# tiny_midi_brk.net
KiCad netlist of a schematic drawn in EAGLE
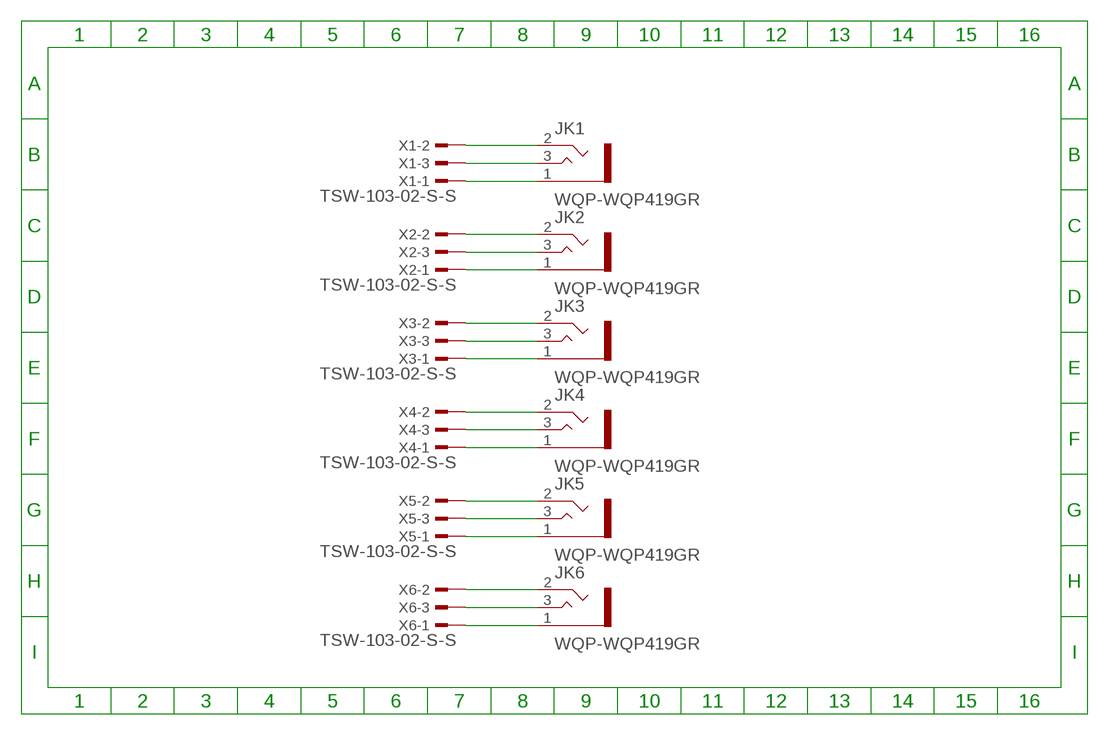
[diagram p0: schematic, sheet 1]

(export (version "E")
  (design (tool "Eeschema 10.0.6"))
  (components
    (comp (ref "JK1")
      (value "WQP-WQP419GR")
      (footprint "eagle-import:WQP-PJ301M-12_JACK_TRS")
      (libsource (lib "eagle-import") (part "WQP-WQP419GR"))
    )
    (comp (ref "JK2")
      (value "WQP-WQP419GR")
      (footprint "eagle-import:WQP-PJ301M-12_JACK_TRS")
      (libsource (lib "eagle-import") (part "WQP-WQP419GR"))
    )
    (comp (ref "JK3")
      (value "WQP-WQP419GR")
      (footprint "eagle-import:WQP-PJ301M-12_JACK_TRS")
      (libsource (lib "eagle-import") (part "WQP-WQP419GR"))
    )
    (comp (ref "JK4")
      (value "WQP-WQP419GR")
      (footprint "eagle-import:WQP-PJ301M-12_JACK_TRS")
      (libsource (lib "eagle-import") (part "WQP-WQP419GR"))
    )
    (comp (ref "JK5")
      (value "WQP-WQP419GR")
      (footprint "eagle-import:WQP-PJ301M-12_JACK_TRS")
      (libsource (lib "eagle-import") (part "WQP-WQP419GR"))
    )
    (comp (ref "JK6")
      (value "WQP-WQP419GR")
      (footprint "eagle-import:WQP-PJ301M-12_JACK_TRS")
      (libsource (lib "eagle-import") (part "WQP-WQP419GR"))
    )
    (comp (ref "X1")
      (value "TSW-103-02-S-S")
      (footprint "eagle-import:TSW-103-02-S-S")
      (libsource (lib "eagle-import") (part "TSW-103-02-S-S"))
    )
    (comp (ref "X2")
      (value "TSW-103-02-S-S")
      (footprint "eagle-import:TSW-103-02-S-S")
      (libsource (lib "eagle-import") (part "TSW-103-02-S-S"))
    )
    (comp (ref "X3")
      (value "TSW-103-02-S-S")
      (footprint "eagle-import:TSW-103-02-S-S")
      (libsource (lib "eagle-import") (part "TSW-103-02-S-S"))
    )
    (comp (ref "X4")
      (value "TSW-103-02-S-S")
      (footprint "eagle-import:TSW-103-02-S-S")
      (libsource (lib "eagle-import") (part "TSW-103-02-S-S"))
    )
    (comp (ref "X5")
      (value "TSW-103-02-S-S")
      (footprint "eagle-import:TSW-103-02-S-S")
      (libsource (lib "eagle-import") (part "TSW-103-02-S-S"))
    )
    (comp (ref "X6")
      (value "TSW-103-02-S-S")
      (footprint "eagle-import:TSW-103-02-S-S")
      (libsource (lib "eagle-import") (part "TSW-103-02-S-S"))
    )
  )
  (nets
    (net (code "1") (name "Net-(JK1-Pad1)") (class "Default")
      (node (ref "JK1") (pin "1") (pinfunction "1_1") (pintype "passive"))
      (node (ref "X1") (pin "1") (pinfunction "1_1") (pintype "passive"))
    )
    (net (code "2") (name "Net-(JK2-Pad1)") (class "Default")
      (node (ref "JK2") (pin "1") (pinfunction "1_1") (pintype "passive"))
      (node (ref "X2") (pin "1") (pinfunction "1_1") (pintype "passive"))
    )
    (net (code "3") (name "Net-(JK3-Pad1)") (class "Default")
      (node (ref "JK3") (pin "1") (pinfunction "1_1") (pintype "passive"))
      (node (ref "X3") (pin "1") (pinfunction "1_1") (pintype "passive"))
    )
    (net (code "4") (name "Net-(JK4-Pad1)") (class "Default")
      (node (ref "JK4") (pin "1") (pinfunction "1_1") (pintype "passive"))
      (node (ref "X4") (pin "1") (pinfunction "1_1") (pintype "passive"))
    )
    (net (code "5") (name "Net-(JK5-Pad1)") (class "Default")
      (node (ref "JK5") (pin "1") (pinfunction "1_1") (pintype "passive"))
      (node (ref "X5") (pin "1") (pinfunction "1_1") (pintype "passive"))
    )
    (net (code "6") (name "Net-(JK6-Pad1)") (class "Default")
      (node (ref "JK6") (pin "1") (pinfunction "1_1") (pintype "passive"))
      (node (ref "X6") (pin "1") (pinfunction "1_1") (pintype "passive"))
    )
    (net (code "7") (name "Net-(X1B-1)") (class "Default")
      (node (ref "JK1") (pin "2") (pinfunction "2_2") (pintype "passive"))
      (node (ref "X1") (pin "2") (pinfunction "1_2") (pintype "passive"))
    )
    (net (code "8") (name "Net-(X1C-1)") (class "Default")
      (node (ref "JK1") (pin "3") (pinfunction "3_3") (pintype "passive"))
      (node (ref "X1") (pin "3") (pinfunction "1_3") (pintype "passive"))
    )
    (net (code "9") (name "Net-(X2B-1)") (class "Default")
      (node (ref "JK2") (pin "2") (pinfunction "2_2") (pintype "passive"))
      (node (ref "X2") (pin "2") (pinfunction "1_2") (pintype "passive"))
    )
    (net (code "10") (name "Net-(X2C-1)") (class "Default")
      (node (ref "JK2") (pin "3") (pinfunction "3_3") (pintype "passive"))
      (node (ref "X2") (pin "3") (pinfunction "1_3") (pintype "passive"))
    )
    (net (code "11") (name "Net-(X3B-1)") (class "Default")
      (node (ref "JK3") (pin "2") (pinfunction "2_2") (pintype "passive"))
      (node (ref "X3") (pin "2") (pinfunction "1_2") (pintype "passive"))
    )
    (net (code "12") (name "Net-(X3C-1)") (class "Default")
      (node (ref "JK3") (pin "3") (pinfunction "3_3") (pintype "passive"))
      (node (ref "X3") (pin "3") (pinfunction "1_3") (pintype "passive"))
    )
    (net (code "13") (name "Net-(X4B-1)") (class "Default")
      (node (ref "JK4") (pin "2") (pinfunction "2_2") (pintype "passive"))
      (node (ref "X4") (pin "2") (pinfunction "1_2") (pintype "passive"))
    )
    (net (code "14") (name "Net-(X4C-1)") (class "Default")
      (node (ref "JK4") (pin "3") (pinfunction "3_3") (pintype "passive"))
      (node (ref "X4") (pin "3") (pinfunction "1_3") (pintype "passive"))
    )
    (net (code "15") (name "Net-(X5B-1)") (class "Default")
      (node (ref "JK5") (pin "2") (pinfunction "2_2") (pintype "passive"))
      (node (ref "X5") (pin "2") (pinfunction "1_2") (pintype "passive"))
    )
    (net (code "16") (name "Net-(X5C-1)") (class "Default")
      (node (ref "JK5") (pin "3") (pinfunction "3_3") (pintype "passive"))
      (node (ref "X5") (pin "3") (pinfunction "1_3") (pintype "passive"))
    )
    (net (code "17") (name "Net-(X6B-1)") (class "Default")
      (node (ref "JK6") (pin "2") (pinfunction "2_2") (pintype "passive"))
      (node (ref "X6") (pin "2") (pinfunction "1_2") (pintype "passive"))
    )
    (net (code "18") (name "Net-(X6C-1)") (class "Default")
      (node (ref "JK6") (pin "3") (pinfunction "3_3") (pintype "passive"))
      (node (ref "X6") (pin "3") (pinfunction "1_3") (pintype "passive"))
    )
  )
)
